# 2_way_splitter.net
KiCad netlist of a schematic drawn in Altium Designer
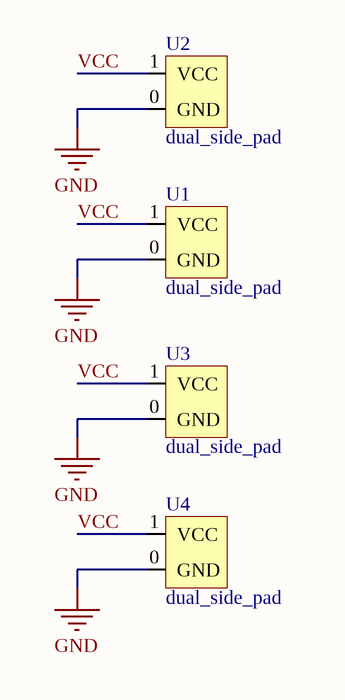
[diagram p0: 2_way_splitter.SchDoc]

(export (version "E")
  (design (tool "Eeschema 10.0.6"))
  (components
    (comp (ref "U1")
      (value "dual_side_pad")
      (footprint "dual_side_pad")
      (libsource (lib "2_way_splitter") (part "dual_side_pad"))
    )
    (comp (ref "U2")
      (value "dual_side_pad")
      (footprint "dual_side_pad")
      (libsource (lib "2_way_splitter") (part "dual_side_pad"))
    )
    (comp (ref "U3")
      (value "dual_side_pad")
      (footprint "dual_side_pad")
      (libsource (lib "2_way_splitter") (part "dual_side_pad"))
    )
    (comp (ref "U4")
      (value "dual_side_pad")
      (footprint "dual_side_pad")
      (libsource (lib "2_way_splitter") (part "dual_side_pad"))
    )
  )
  (nets
    (net (code "1") (name "/VCC") (class "Default")
      (node (ref "U1") (pin "1") (pinfunction "VCC_1") (pintype "passive"))
      (node (ref "U2") (pin "1") (pinfunction "VCC_1") (pintype "passive"))
      (node (ref "U3") (pin "1") (pinfunction "VCC_1") (pintype "passive"))
      (node (ref "U4") (pin "1") (pinfunction "VCC_1") (pintype "passive"))
    )
    (net (code "2") (name "GND") (class "Default")
      (node (ref "U1") (pin "0") (pinfunction "GND_0") (pintype "passive"))
      (node (ref "U2") (pin "0") (pinfunction "GND_0") (pintype "passive"))
      (node (ref "U3") (pin "0") (pinfunction "GND_0") (pintype "passive"))
      (node (ref "U4") (pin "0") (pinfunction "GND_0") (pintype "passive"))
    )
  )
)
